# Hava_Durumu_st_V1_0.net
KiCad netlist of a schematic drawn in EAGLE
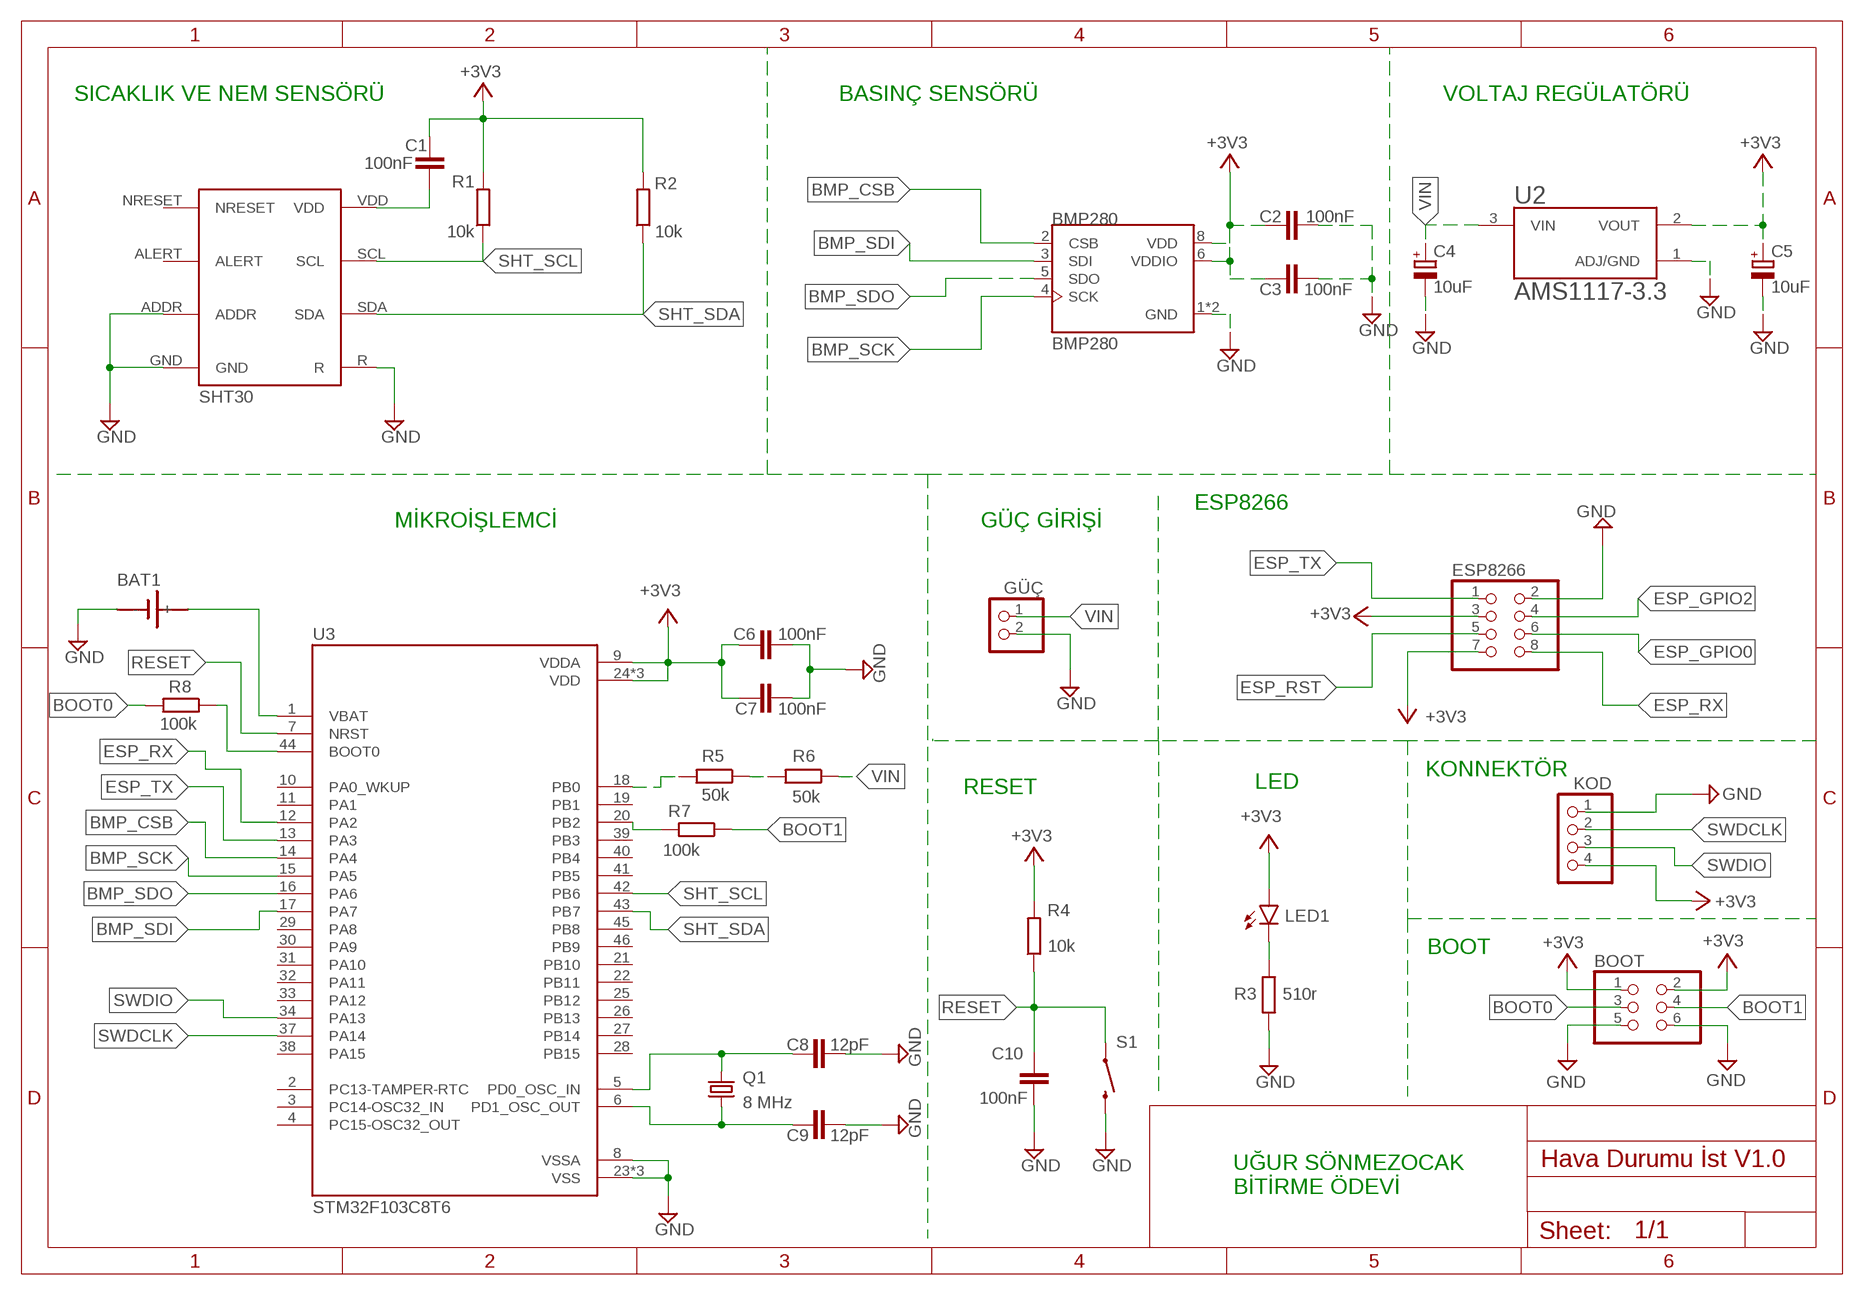
[diagram p0: schematic, sheet 1]

(export (version "E")
  (design (tool "Eeschema 10.0.6"))
  (components
    (comp (ref "BAT1")
      (value "SN2032")
      (footprint "eagle-import:SN2032")
      (libsource (lib "eagle-import") (part "SN2032"))
    )
    (comp (ref "BMP280")
      (value "BMP280")
      (footprint "eagle-import:XDCR_BMP280")
      (fields (field (name "MF") "Bosch"))
      (libsource (lib "eagle-import") (part "BMP280"))
    )
    (comp (ref "BOOT")
      (value "PINHD-2X3")
      (footprint "eagle-import:2X03")
      (libsource (lib "eagle-import") (part "PINHD-2X3"))
    )
    (comp (ref "C1")
      (value "100nF")
      (footprint "eagle-import:C0805")
      (libsource (lib "eagle-import") (part "C-EUC0805"))
    )
    (comp (ref "C2")
      (value "100nF")
      (footprint "eagle-import:C0805")
      (libsource (lib "eagle-import") (part "C-EUC0805"))
    )
    (comp (ref "C3")
      (value "100nF")
      (footprint "eagle-import:C0805")
      (libsource (lib "eagle-import") (part "C-EUC0805"))
    )
    (comp (ref "C4")
      (value "10uF")
      (footprint "eagle-import:SMC_P")
      (libsource (lib "eagle-import") (part "CPOL-EUSMCP"))
    )
    (comp (ref "C5")
      (value "10uF")
      (footprint "eagle-import:SMC_P")
      (libsource (lib "eagle-import") (part "CPOL-EUSMCP"))
    )
    (comp (ref "C6")
      (value "100nF")
      (footprint "eagle-import:C0805")
      (libsource (lib "eagle-import") (part "C-EUC0805"))
    )
    (comp (ref "C7")
      (value "100nF")
      (footprint "eagle-import:C0805")
      (libsource (lib "eagle-import") (part "C-EUC0805"))
    )
    (comp (ref "C8")
      (value "12pF")
      (footprint "eagle-import:C0805")
      (libsource (lib "eagle-import") (part "C-EUC0805"))
    )
    (comp (ref "C9")
      (value "12pF")
      (footprint "eagle-import:C0805")
      (libsource (lib "eagle-import") (part "C-EUC0805"))
    )
    (comp (ref "C10")
      (value "100nF")
      (footprint "eagle-import:C0805")
      (libsource (lib "eagle-import") (part "C-EUC0805"))
    )
    (comp (ref "ESP8266")
      (value "PINHD-2X4")
      (footprint "eagle-import:2X04")
      (libsource (lib "eagle-import") (part "PINHD-2X4"))
    )
    (comp (ref "GÜÇ")
      (value "PINHD-1X2")
      (footprint "eagle-import:1X02")
      (libsource (lib "eagle-import") (part "PINHD-1X2"))
    )
    (comp (ref "KOD")
      (value "PINHD-1X4/90")
      (footprint "eagle-import:1X04_90")
      (libsource (lib "eagle-import") (part "PINHD-1X4/90"))
    )
    (comp (ref "LED1")
      (value "LEDCHIP-LED0805")
      (footprint "eagle-import:CHIP-LED0805")
      (libsource (lib "eagle-import") (part "LEDCHIP-LED0805"))
    )
    (comp (ref "Q1")
      (value "8 MHz")
      (footprint "eagle-import:HC49UP")
      (libsource (lib "eagle-import") (part "CRYSTALHC49UP"))
    )
    (comp (ref "R1")
      (value "10k")
      (footprint "eagle-import:R0805")
      (libsource (lib "eagle-import") (part "R-EU_R0805"))
    )
    (comp (ref "R2")
      (value "10k")
      (footprint "eagle-import:R0805")
      (libsource (lib "eagle-import") (part "R-EU_R0805"))
    )
    (comp (ref "R3")
      (value "510r")
      (footprint "eagle-import:R0805")
      (libsource (lib "eagle-import") (part "R-EU_R0805"))
    )
    (comp (ref "R4")
      (value "10k")
      (footprint "eagle-import:R0805")
      (libsource (lib "eagle-import") (part "R-EU_R0805"))
    )
    (comp (ref "R5")
      (value "50k")
      (footprint "eagle-import:R0805")
      (libsource (lib "eagle-import") (part "R-EU_R0805"))
    )
    (comp (ref "R6")
      (value "50k")
      (footprint "eagle-import:R0805")
      (libsource (lib "eagle-import") (part "R-EU_R0805"))
    )
    (comp (ref "R7")
      (value "100k")
      (footprint "eagle-import:R0805")
      (libsource (lib "eagle-import") (part "R-EU_R0805"))
    )
    (comp (ref "R8")
      (value "100k")
      (footprint "eagle-import:R0805")
      (libsource (lib "eagle-import") (part "R-EU_R0805"))
    )
    (comp (ref "S1")
      (value "MOMENTARY-SWITCH-SPST-PTH-6.0MM")
      (footprint "eagle-import:TACTILE_SWITCH_PTH_6.0MM")
      (libsource (lib "eagle-import") (part "MOMENTARY-SWITCH-SPST-PTH-6.0MM"))
    )
    (comp (ref "U$1")
      (value "SHT30")
      (footprint "eagle-import:SON50P250X250X90-9T100X170N")
      (libsource (lib "eagle-import") (part "SHT30"))
    )
    (comp (ref "U2")
      (value "AMS1117-3.3")
      (footprint "eagle-import:SOT229P700X180-4N")
      (fields (field (name "MF") "Advanced Monolithic Systems"))
      (libsource (lib "eagle-import") (part "AMS1117-3.3"))
    )
    (comp (ref "U3")
      (value "STM32F103C8T6")
      (footprint "eagle-import:QFP50P900X900X160-48N")
      (fields (field (name "MF") "STMicroelectronics"))
      (libsource (lib "eagle-import") (part "STM32F103C8T6"))
    )
  )
  (nets
    (net (code "1") (name "+3V3") (class "Default")
      (node (ref "BMP280") (pin "6") (pinfunction "VDDIO_6") (pintype "power_in"))
      (node (ref "BMP280") (pin "8") (pinfunction "VDD_8") (pintype "power_in"))
      (node (ref "BOOT") (pin "1") (pinfunction "1_1") (pintype "passive"))
      (node (ref "BOOT") (pin "2") (pinfunction "2_2") (pintype "passive"))
      (node (ref "C1") (pin "1") (pinfunction "1_1") (pintype "passive"))
      (node (ref "C2") (pin "1") (pinfunction "1_1") (pintype "passive"))
      (node (ref "C3") (pin "1") (pinfunction "1_1") (pintype "passive"))
      (node (ref "C5") (pin "+") (pinfunction "+_+") (pintype "passive"))
      (node (ref "C6") (pin "1") (pinfunction "1_1") (pintype "passive"))
      (node (ref "C7") (pin "1") (pinfunction "1_1") (pintype "passive"))
      (node (ref "ESP8266") (pin "3") (pinfunction "3_3") (pintype "passive"))
      (node (ref "ESP8266") (pin "7") (pinfunction "7_7") (pintype "passive"))
      (node (ref "KOD") (pin "4") (pinfunction "4_4") (pintype "passive"))
      (node (ref "LED1") (pin "A") (pinfunction "A_A") (pintype "passive"))
      (node (ref "R1") (pin "2") (pinfunction "2_2") (pintype "passive"))
      (node (ref "R2") (pin "2") (pinfunction "2_2") (pintype "passive"))
      (node (ref "R4") (pin "2") (pinfunction "2_2") (pintype "passive"))
      (node (ref "U2") (pin "2") (pinfunction "VOUT_2") (pintype "output"))
      (node (ref "U3") (pin "24") (pinfunction "VDD_24") (pintype "power_in"))
      (node (ref "U3") (pin "36") (pinfunction "VDD_36") (pintype "power_in"))
      (node (ref "U3") (pin "48") (pinfunction "VDD_48") (pintype "power_in"))
      (node (ref "U3") (pin "9") (pinfunction "VDDA_9") (pintype "power_in"))
    )
    (net (code "2") (name "BMP_CSB") (class "Default")
      (node (ref "BMP280") (pin "2") (pinfunction "CSB_2") (pintype "input"))
      (node (ref "U3") (pin "14") (pinfunction "PA4_14") (pintype "bidirectional"))
    )
    (net (code "3") (name "BMP_SCK") (class "Default")
      (node (ref "BMP280") (pin "4") (pinfunction "SCK_4") (pintype "input"))
      (node (ref "U3") (pin "15") (pinfunction "PA5_15") (pintype "bidirectional"))
    )
    (net (code "4") (name "BMP_SDI") (class "Default")
      (node (ref "BMP280") (pin "3") (pinfunction "SDI_3") (pintype "bidirectional"))
      (node (ref "U3") (pin "17") (pinfunction "PA7_17") (pintype "bidirectional"))
    )
    (net (code "5") (name "BMP_SDO") (class "Default")
      (node (ref "BMP280") (pin "5") (pinfunction "SDO_5") (pintype "bidirectional"))
      (node (ref "U3") (pin "16") (pinfunction "PA6_16") (pintype "bidirectional"))
    )
    (net (code "6") (name "BOOT0") (class "Default")
      (node (ref "BOOT") (pin "3") (pinfunction "3_3") (pintype "passive"))
      (node (ref "R8") (pin "2") (pinfunction "2_2") (pintype "passive"))
    )
    (net (code "7") (name "BOOT1") (class "Default")
      (node (ref "BOOT") (pin "4") (pinfunction "4_4") (pintype "passive"))
      (node (ref "R7") (pin "1") (pinfunction "1_1") (pintype "passive"))
    )
    (net (code "8") (name "ESP_GPIO0") (class "Default")
      (node (ref "ESP8266") (pin "6") (pinfunction "6_6") (pintype "passive"))
    )
    (net (code "9") (name "ESP_GPIO2") (class "Default")
      (node (ref "ESP8266") (pin "4") (pinfunction "4_4") (pintype "passive"))
    )
    (net (code "10") (name "ESP_RST") (class "Default")
      (node (ref "ESP8266") (pin "5") (pinfunction "5_5") (pintype "passive"))
    )
    (net (code "11") (name "ESP_RX") (class "Default")
      (node (ref "ESP8266") (pin "8") (pinfunction "8_8") (pintype "passive"))
      (node (ref "U3") (pin "12") (pinfunction "PA2_12") (pintype "bidirectional"))
    )
    (net (code "12") (name "ESP_TX") (class "Default")
      (node (ref "ESP8266") (pin "1") (pinfunction "1_1") (pintype "passive"))
      (node (ref "U3") (pin "13") (pinfunction "PA3_13") (pintype "bidirectional"))
    )
    (net (code "13") (name "GND") (class "Default")
      (node (ref "BAT1") (pin "-") (pinfunction "-_-") (pintype "passive"))
      (node (ref "BMP280") (pin "1") (pinfunction "GND_1") (pintype "power_in"))
      (node (ref "BMP280") (pin "7") (pinfunction "GND_7") (pintype "power_in"))
      (node (ref "BOOT") (pin "5") (pinfunction "5_5") (pintype "passive"))
      (node (ref "BOOT") (pin "6") (pinfunction "6_6") (pintype "passive"))
      (node (ref "C10") (pin "1") (pinfunction "1_1") (pintype "passive"))
      (node (ref "C2") (pin "2") (pinfunction "2_2") (pintype "passive"))
      (node (ref "C3") (pin "2") (pinfunction "2_2") (pintype "passive"))
      (node (ref "C4") (pin "-") (pinfunction "-_-") (pintype "passive"))
      (node (ref "C5") (pin "-") (pinfunction "-_-") (pintype "passive"))
      (node (ref "C6") (pin "2") (pinfunction "2_2") (pintype "passive"))
      (node (ref "C7") (pin "2") (pinfunction "2_2") (pintype "passive"))
      (node (ref "C8") (pin "2") (pinfunction "2_2") (pintype "passive"))
      (node (ref "C9") (pin "2") (pinfunction "2_2") (pintype "passive"))
      (node (ref "ESP8266") (pin "2") (pinfunction "2_2") (pintype "passive"))
      (node (ref "GÜÇ") (pin "2") (pinfunction "2_2") (pintype "passive"))
      (node (ref "KOD") (pin "1") (pinfunction "1_1") (pintype "passive"))
      (node (ref "R3") (pin "1") (pinfunction "1_1") (pintype "passive"))
      (node (ref "S1") (pin "3") (pinfunction "2_3") (pintype "passive"))
      (node (ref "U$1") (pin "ADDR") (pinfunction "ADDR_ADDR") (pintype "input"))
      (node (ref "U$1") (pin "GND") (pinfunction "GND_GND") (pintype "power_in"))
      (node (ref "U$1") (pin "R") (pinfunction "R_R") (pintype "bidirectional"))
      (node (ref "U2") (pin "1") (pinfunction "ADJ/GND_1") (pintype "power_in"))
      (node (ref "U3") (pin "23") (pinfunction "VSS_23") (pintype "power_in"))
      (node (ref "U3") (pin "35") (pinfunction "VSS_35") (pintype "power_in"))
      (node (ref "U3") (pin "47") (pinfunction "VSS_47") (pintype "power_in"))
      (node (ref "U3") (pin "8") (pinfunction "VSSA_8") (pintype "power_in"))
    )
    (net (code "14") (name "Net-(C1-Pad2)") (class "Default")
      (node (ref "C1") (pin "2") (pinfunction "2_2") (pintype "passive"))
      (node (ref "U$1") (pin "VDD") (pinfunction "VDD_VDD") (pintype "input"))
    )
    (net (code "15") (name "Net-(LED1-PadC)") (class "Default")
      (node (ref "LED1") (pin "C") (pinfunction "C_C") (pintype "passive"))
      (node (ref "R3") (pin "2") (pinfunction "2_2") (pintype "passive"))
    )
    (net (code "16") (name "Net-(R5-Pad1)") (class "Default")
      (node (ref "R5") (pin "1") (pinfunction "1_1") (pintype "passive"))
      (node (ref "R6") (pin "2") (pinfunction "2_2") (pintype "passive"))
    )
    (net (code "17") (name "Net-(U3-BOOT0)") (class "Default")
      (node (ref "R8") (pin "1") (pinfunction "1_1") (pintype "passive"))
      (node (ref "U3") (pin "44") (pinfunction "BOOT0_44") (pintype "input"))
    )
    (net (code "18") (name "Net-(U3-PB0)") (class "Default")
      (node (ref "R5") (pin "2") (pinfunction "2_2") (pintype "passive"))
      (node (ref "U3") (pin "18") (pinfunction "PB0_18") (pintype "bidirectional"))
    )
    (net (code "19") (name "Net-(U3-PB2)") (class "Default")
      (node (ref "R7") (pin "2") (pinfunction "2_2") (pintype "passive"))
      (node (ref "U3") (pin "20") (pinfunction "PB2_20") (pintype "bidirectional"))
    )
    (net (code "20") (name "Net-(U3-PD0_OSC_IN)") (class "Default")
      (node (ref "C8") (pin "1") (pinfunction "1_1") (pintype "passive"))
      (node (ref "Q1") (pin "2") (pinfunction "2_2") (pintype "passive"))
      (node (ref "U3") (pin "5") (pinfunction "PD0_OSC_IN_5") (pintype "bidirectional"))
    )
    (net (code "21") (name "Net-(U3-PD1_OSC_OUT)") (class "Default")
      (node (ref "C9") (pin "1") (pinfunction "1_1") (pintype "passive"))
      (node (ref "Q1") (pin "1") (pinfunction "1_1") (pintype "passive"))
      (node (ref "U3") (pin "6") (pinfunction "PD1_OSC_OUT_6") (pintype "bidirectional"))
    )
    (net (code "22") (name "Net-(U3-VBAT)") (class "Default")
      (node (ref "BAT1") (pin "+") (pinfunction "+_+") (pintype "passive"))
      (node (ref "U3") (pin "1") (pinfunction "VBAT_1") (pintype "bidirectional"))
    )
    (net (code "23") (name "RESET") (class "Default")
      (node (ref "C10") (pin "2") (pinfunction "2_2") (pintype "passive"))
      (node (ref "R4") (pin "1") (pinfunction "1_1") (pintype "passive"))
      (node (ref "S1") (pin "1") (pinfunction "1_1") (pintype "passive"))
      (node (ref "U3") (pin "7") (pinfunction "NRST_7") (pintype "input"))
    )
    (net (code "24") (name "SHT_SCL") (class "Default")
      (node (ref "R1") (pin "1") (pinfunction "1_1") (pintype "passive"))
      (node (ref "U$1") (pin "SCL") (pinfunction "SCL_SCL") (pintype "bidirectional"))
      (node (ref "U3") (pin "42") (pinfunction "PB6_42") (pintype "bidirectional"))
    )
    (net (code "25") (name "SHT_SDA") (class "Default")
      (node (ref "R2") (pin "1") (pinfunction "1_1") (pintype "passive"))
      (node (ref "U$1") (pin "SDA") (pinfunction "SDA_SDA") (pintype "bidirectional"))
      (node (ref "U3") (pin "43") (pinfunction "PB7_43") (pintype "bidirectional"))
    )
    (net (code "26") (name "SWDCLK") (class "Default")
      (node (ref "KOD") (pin "2") (pinfunction "2_2") (pintype "passive"))
      (node (ref "U3") (pin "37") (pinfunction "PA14_37") (pintype "bidirectional"))
    )
    (net (code "27") (name "SWDIO") (class "Default")
      (node (ref "KOD") (pin "3") (pinfunction "3_3") (pintype "passive"))
      (node (ref "U3") (pin "34") (pinfunction "PA13_34") (pintype "bidirectional"))
    )
    (net (code "28") (name "VIN") (class "Default")
      (node (ref "C4") (pin "+") (pinfunction "+_+") (pintype "passive"))
      (node (ref "GÜÇ") (pin "1") (pinfunction "1_1") (pintype "passive"))
      (node (ref "R6") (pin "1") (pinfunction "1_1") (pintype "passive"))
      (node (ref "U2") (pin "3") (pinfunction "VIN_3") (pintype "input"))
    )
    (net (code "29") (name "unconnected-(U$1-PadALERT)") (class "Default")
      (node (ref "U$1") (pin "ALERT") (pinfunction "ALERT_ALERT") (pintype "output"))
    )
    (net (code "30") (name "unconnected-(U$1-PadNRESET)") (class "Default")
      (node (ref "U$1") (pin "NRESET") (pinfunction "NRESET_NRESET") (pintype "input"))
    )
    (net (code "31") (name "unconnected-(U3-PA0_WKUP-Pad10)") (class "Default")
      (node (ref "U3") (pin "10") (pinfunction "PA0_WKUP_10") (pintype "bidirectional"))
    )
    (net (code "32") (name "unconnected-(U3-PA1-Pad11)") (class "Default")
      (node (ref "U3") (pin "11") (pinfunction "PA1_11") (pintype "bidirectional"))
    )
    (net (code "33") (name "unconnected-(U3-PA8-Pad29)") (class "Default")
      (node (ref "U3") (pin "29") (pinfunction "PA8_29") (pintype "bidirectional"))
    )
    (net (code "34") (name "unconnected-(U3-PA9-Pad30)") (class "Default")
      (node (ref "U3") (pin "30") (pinfunction "PA9_30") (pintype "bidirectional"))
    )
    (net (code "35") (name "unconnected-(U3-PA10-Pad31)") (class "Default")
      (node (ref "U3") (pin "31") (pinfunction "PA10_31") (pintype "bidirectional"))
    )
    (net (code "36") (name "unconnected-(U3-PA11-Pad32)") (class "Default")
      (node (ref "U3") (pin "32") (pinfunction "PA11_32") (pintype "bidirectional"))
    )
    (net (code "37") (name "unconnected-(U3-PA12-Pad33)") (class "Default")
      (node (ref "U3") (pin "33") (pinfunction "PA12_33") (pintype "bidirectional"))
    )
    (net (code "38") (name "unconnected-(U3-PA15-Pad38)") (class "Default")
      (node (ref "U3") (pin "38") (pinfunction "PA15_38") (pintype "bidirectional"))
    )
    (net (code "39") (name "unconnected-(U3-PB1-Pad19)") (class "Default")
      (node (ref "U3") (pin "19") (pinfunction "PB1_19") (pintype "bidirectional"))
    )
    (net (code "40") (name "unconnected-(U3-PB3-Pad39)") (class "Default")
      (node (ref "U3") (pin "39") (pinfunction "PB3_39") (pintype "bidirectional"))
    )
    (net (code "41") (name "unconnected-(U3-PB4-Pad40)") (class "Default")
      (node (ref "U3") (pin "40") (pinfunction "PB4_40") (pintype "bidirectional"))
    )
    (net (code "42") (name "unconnected-(U3-PB5-Pad41)") (class "Default")
      (node (ref "U3") (pin "41") (pinfunction "PB5_41") (pintype "bidirectional"))
    )
    (net (code "43") (name "unconnected-(U3-PB8-Pad45)") (class "Default")
      (node (ref "U3") (pin "45") (pinfunction "PB8_45") (pintype "bidirectional"))
    )
    (net (code "44") (name "unconnected-(U3-PB9-Pad46)") (class "Default")
      (node (ref "U3") (pin "46") (pinfunction "PB9_46") (pintype "bidirectional"))
    )
    (net (code "45") (name "unconnected-(U3-PB10-Pad21)") (class "Default")
      (node (ref "U3") (pin "21") (pinfunction "PB10_21") (pintype "bidirectional"))
    )
    (net (code "46") (name "unconnected-(U3-PB11-Pad22)") (class "Default")
      (node (ref "U3") (pin "22") (pinfunction "PB11_22") (pintype "bidirectional"))
    )
    (net (code "47") (name "unconnected-(U3-PB12-Pad25)") (class "Default")
      (node (ref "U3") (pin "25") (pinfunction "PB12_25") (pintype "bidirectional"))
    )
    (net (code "48") (name "unconnected-(U3-PB13-Pad26)") (class "Default")
      (node (ref "U3") (pin "26") (pinfunction "PB13_26") (pintype "bidirectional"))
    )
    (net (code "49") (name "unconnected-(U3-PB14-Pad27)") (class "Default")
      (node (ref "U3") (pin "27") (pinfunction "PB14_27") (pintype "bidirectional"))
    )
    (net (code "50") (name "unconnected-(U3-PB15-Pad28)") (class "Default")
      (node (ref "U3") (pin "28") (pinfunction "PB15_28") (pintype "bidirectional"))
    )
    (net (code "51") (name "unconnected-(U3-PC13-TAMPER-RTC-Pad2)") (class "Default")
      (node (ref "U3") (pin "2") (pinfunction "PC13-TAMPER-RTC_2") (pintype "bidirectional"))
    )
    (net (code "52") (name "unconnected-(U3-PC14-OSC32_IN-Pad3)") (class "Default")
      (node (ref "U3") (pin "3") (pinfunction "PC14-OSC32_IN_3") (pintype "bidirectional"))
    )
    (net (code "53") (name "unconnected-(U3-PC15-OSC32_OUT-Pad4)") (class "Default")
      (node (ref "U3") (pin "4") (pinfunction "PC15-OSC32_OUT_4") (pintype "bidirectional"))
    )
  )
)
